# Transimpedance.net
KiCad netlist of a schematic drawn in Altium Designer
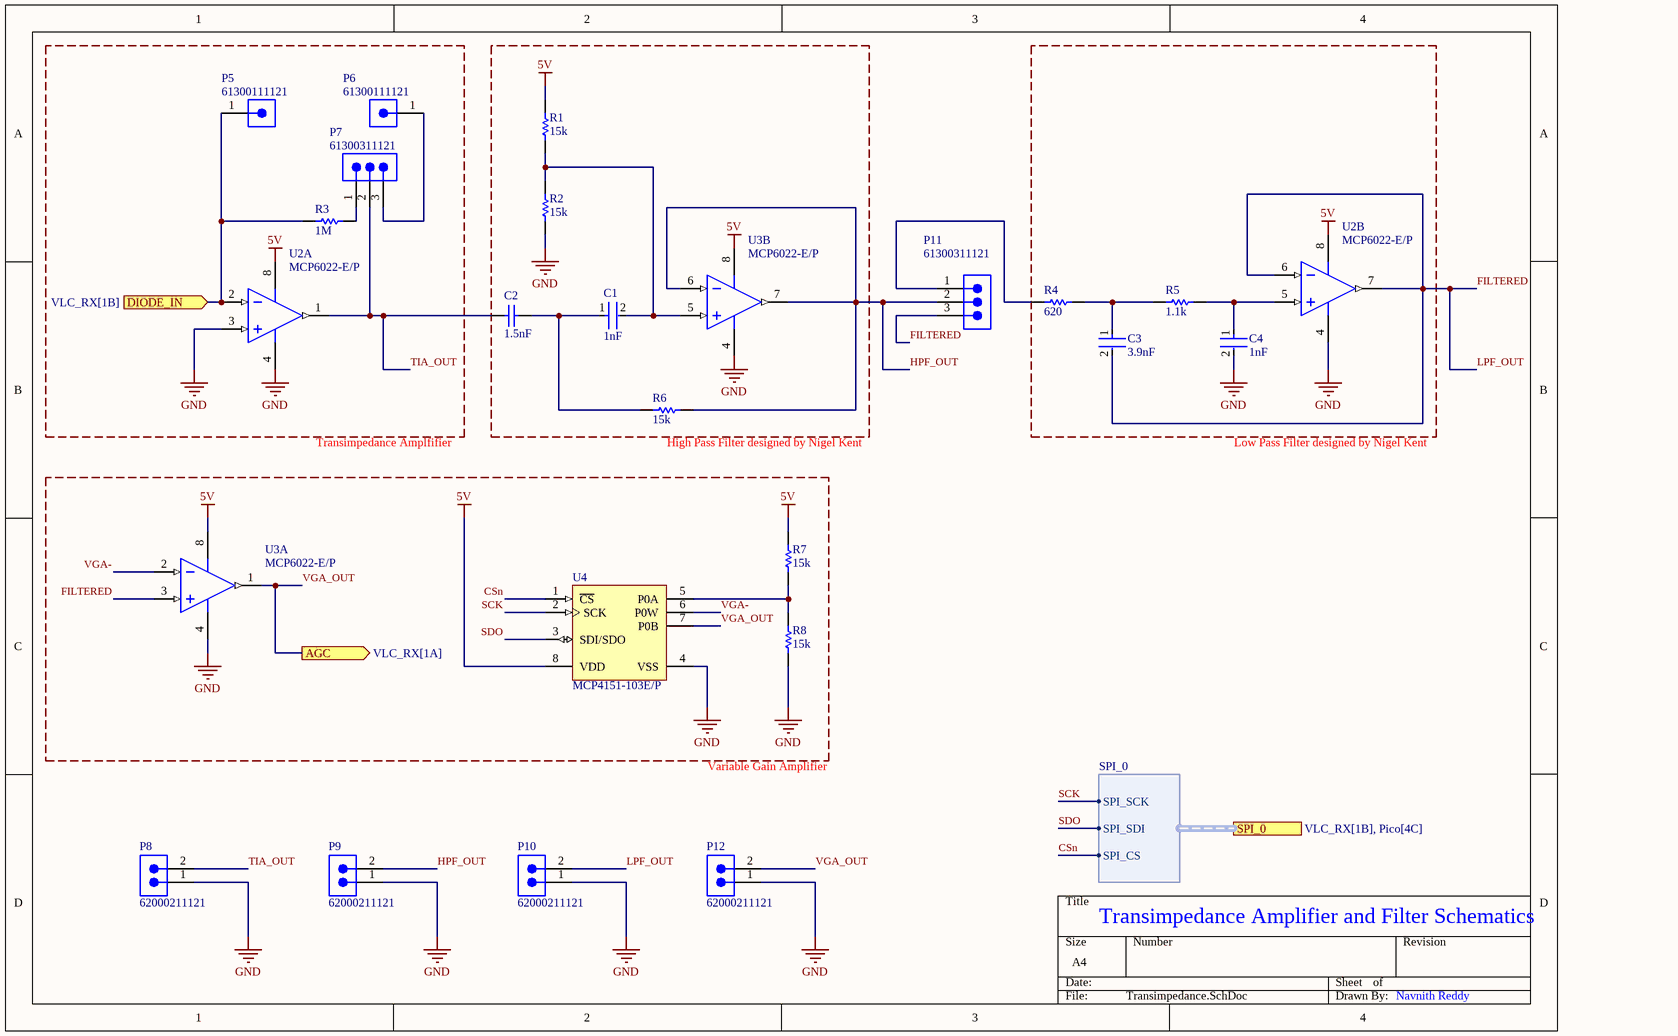
[diagram p0: Transimpedance.SchDoc]

(export (version "E")
  (design (tool "Eeschema 10.0.6"))
  (components
    (comp (ref "C1")
      (value "1nF")
      (footprint "FP-0805-L_2_01_0_2-W_1_25-IPC_C")
      (description "General Purpose Ceramic Capacitor, 0805, 1nF, 10%, X7R, 0.15, 50V")
      (fields (field (name "VOLTAGE") "50V") (field (name "TOLERANCE") "10%"))
      (libsource (lib "Altium Content Vault") (part "02cd4be3c70576c341d710602a673aa"))
    )
    (comp (ref "C2")
      (value "1.5nF")
      (footprint "CAPC2013X94X50ML20T25")
      (fields
        (field (name "MANUFACTURER") "AVX Interconnect / Elco")
        (field (name "PART NUMBER") "08051C152KAT2A")
      )
      (libsource (lib "Altium Content Vault") (part "CAP"))
    )
    (comp (ref "C3")
      (value "3.9nF")
      (footprint "FP-C0805C-DN-MFG")
      (description "C0805 3,900 pF C0G 30ppm/°C 5.00% 200 V")
      (fields (field (name "MANUFACTURER PART NUMBER") "C0805C392J2GACAUTO"))
      (libsource (lib "Altium Content Vault") (part "b4654b650e69147ec39a6b967a45e02"))
    )
    (comp (ref "C4")
      (value "1nF")
      (footprint "FP-0805-L_2_01_0_2-W_1_25-IPC_C")
      (description "General Purpose Ceramic Capacitor, 0805, 1nF, 10%, X7R, 0.15, 50V")
      (fields (field (name "VOLTAGE") "50V") (field (name "TOLERANCE") "10%"))
      (libsource (lib "Altium Content Vault") (part "02cd4be3c70576c341d710602a673aa"))
    )
    (comp (ref "P5")
      (value "61300111121")
      (footprint "61300111121")
      (libsource (lib "Altium Content Vault") (part "Header_Male_1R_01P"))
    )
    (comp (ref "P6")
      (value "61300111121")
      (footprint "61300111121")
      (libsource (lib "Altium Content Vault") (part "Header_Male_1R_01P"))
    )
    (comp (ref "P7")
      (value "61300311121")
      (footprint "61300311121")
      (libsource (lib "Altium Content Vault") (part "Header_Male_1R_03P"))
    )
    (comp (ref "P8")
      (value "62000211121")
      (footprint "62000211121")
      (libsource (lib "Altium Content Vault") (part "Header_Male_1R_02P"))
    )
    (comp (ref "P9")
      (value "62000211121")
      (footprint "62000211121")
      (libsource (lib "Altium Content Vault") (part "Header_Male_1R_02P"))
    )
    (comp (ref "P10")
      (value "62000211121")
      (footprint "62000211121")
      (libsource (lib "Altium Content Vault") (part "Header_Male_1R_02P"))
    )
    (comp (ref "P11")
      (value "61300311121")
      (footprint "61300311121")
      (libsource (lib "Altium Content Vault") (part "Header_Male_1R_03P"))
    )
    (comp (ref "P12")
      (value "62000211121")
      (footprint "62000211121")
      (libsource (lib "Altium Content Vault") (part "Header_Male_1R_02P"))
    )
    (comp (ref "R1")
      (value "15k")
      (footprint "RESC2013X55X40NL15T20")
      (fields (field (name "PART NUMBER") "TNPW080515K0BEEA") (field (name "MANUFACTURER") "Vishay Dale"))
      (libsource (lib "Altium Content Vault") (part "RES"))
    )
    (comp (ref "R2")
      (value "15k")
      (footprint "RESC2013X55X40NL15T20")
      (fields (field (name "PART NUMBER") "TNPW080515K0BEEA") (field (name "MANUFACTURER") "Vishay Dale"))
      (libsource (lib "Altium Content Vault") (part "RES"))
    )
    (comp (ref "R3")
      (value "1M")
      (footprint "RESC2013X60X40LL20T25")
      (fields (field (name "PART NUMBER") "ERA-6AEB105V") (field (name "MANUFACTURER") "Panasonic"))
      (libsource (lib "Altium Content Vault") (part "RES"))
    )
    (comp (ref "R4")
      (value "620")
      (footprint "RESC2013X70X40LL20T20")
      (fields (field (name "MANUFACTURER") "Panasonic") (field (name "PART NUMBER") "ERJ-6GEYJ621V"))
      (libsource (lib "Altium Content Vault") (part "RES"))
    )
    (comp (ref "R5")
      (value "1.1k")
      (footprint "RESC2013X50X30LL20T20")
      (fields (field (name "PART NUMBER") "CRCW08051K10FKTA") (field (name "MANUFACTURER") "Vishay Dale"))
      (libsource (lib "Altium Content Vault") (part "RES"))
    )
    (comp (ref "R6")
      (value "15k")
      (footprint "RESC2013X55X40NL15T20")
      (fields (field (name "PART NUMBER") "TNPW080515K0BEEA") (field (name "MANUFACTURER") "Vishay Dale"))
      (libsource (lib "Altium Content Vault") (part "RES"))
    )
    (comp (ref "R7")
      (value "15k")
      (footprint "RESC2013X55X40NL15T20")
      (fields (field (name "PART NUMBER") "TNPW080515K0BEEA") (field (name "MANUFACTURER") "Vishay Dale"))
      (libsource (lib "Altium Content Vault") (part "RES"))
    )
    (comp (ref "R8")
      (value "15k")
      (footprint "RESC2013X55X40NL15T20")
      (fields (field (name "PART NUMBER") "TNPW080515K0BEEA") (field (name "MANUFACTURER") "Vishay Dale"))
      (libsource (lib "Altium Content Vault") (part "RES"))
    )
    (comp (ref "U2")
      (value "MCP6022-E/P")
      (footprint "PDIP300-P8")
      (description "None")
      (libsource (lib "Altium Content Vault") (part "AMP-OPA-MCP6022-IL8"))
    )
    (comp (ref "U3")
      (value "MCP6022-E/P")
      (footprint "PDIP300-P8")
      (description "None")
      (libsource (lib "Altium Content Vault") (part "AMP-OPA-MCP6022-IL8"))
    )
    (comp (ref "U4")
      (value "MCP4151-103E/P")
      (footprint "PDIP300-P8")
      (description "7/8-Bit Single/Dual SPI Digital POT with Volatile Memory, 8-Pin PDIP, Extended Temperature")
      (libsource (lib "Altium Content Vault") (part "IN-DPOT-MCP41X1-8"))
    )
  )
  (nets
    (net (code "2") (name "/CSn") (class "Default")
      (node (ref "U4") (pin "1") (pinfunction "~{CS}_1") (pintype "input"))
    )
    (net (code "3") (name "/DIODE_IN") (class "Default")
      (node (ref "P5") (pin "1") (pinfunction "1_1") (pintype "passive"))
      (node (ref "R3") (pin "1") (pinfunction "1_1") (pintype "passive"))
      (node (ref "U2") (pin "2") (pinfunction "VINA-_2") (pintype "input"))
    )
    (net (code "4") (name "/FILTERED") (class "Default")
      (node (ref "C3") (pin "2") (pinfunction "2_2") (pintype "passive"))
      (node (ref "P10") (pin "2") (pinfunction "2_2") (pintype "passive"))
      (node (ref "P11") (pin "3") (pinfunction "3_3") (pintype "passive"))
      (node (ref "U2") (pin "6") (pinfunction "VINB-_6") (pintype "input"))
      (node (ref "U2") (pin "7") (pinfunction "VOUTB_7") (pintype "output"))
      (node (ref "U3") (pin "3") (pinfunction "VINA+_3") (pintype "input"))
    )
    (net (code "5") (name "/HPF_OUT") (class "Default")
      (node (ref "P11") (pin "2") (pinfunction "2_2") (pintype "passive"))
      (node (ref "P9") (pin "2") (pinfunction "2_2") (pintype "passive"))
      (node (ref "R6") (pin "2") (pinfunction "2_2") (pintype "passive"))
      (node (ref "U3") (pin "6") (pinfunction "VINB-_6") (pintype "input"))
      (node (ref "U3") (pin "7") (pinfunction "VOUTB_7") (pintype "output"))
    )
    (net (code "6") (name "/SCK") (class "Default")
      (node (ref "U4") (pin "2") (pinfunction "SCK_2") (pintype "input"))
    )
    (net (code "7") (name "/SDO") (class "Default")
      (node (ref "U4") (pin "3") (pinfunction "SDI/SDO_3") (pintype "bidirectional"))
    )
    (net (code "8") (name "/TIA_OUT") (class "Default")
      (node (ref "C2") (pin "1") (pinfunction "1_1") (pintype "passive"))
      (node (ref "P7") (pin "2") (pinfunction "2_2") (pintype "passive"))
      (node (ref "P8") (pin "2") (pinfunction "2_2") (pintype "passive"))
      (node (ref "U2") (pin "1") (pinfunction "VOUTA_1") (pintype "output"))
    )
    (net (code "9") (name "/VGA-") (class "Default")
      (node (ref "U3") (pin "2") (pinfunction "VINA-_2") (pintype "input"))
      (node (ref "U4") (pin "6") (pinfunction "P0W_6") (pintype "passive"))
    )
    (net (code "10") (name "/VGA_OUT") (class "Default")
      (node (ref "P12") (pin "2") (pinfunction "2_2") (pintype "passive"))
      (node (ref "U3") (pin "1") (pinfunction "VOUTA_1") (pintype "output"))
      (node (ref "U4") (pin "7") (pinfunction "P0B_7") (pintype "passive"))
    )
    (net (code "12") (name "5V") (class "Default")
      (node (ref "R1") (pin "2") (pinfunction "2_2") (pintype "passive"))
      (node (ref "R7") (pin "2") (pinfunction "2_2") (pintype "passive"))
      (node (ref "U2") (pin "8") (pinfunction "VDD_8") (pintype "power_in"))
      (node (ref "U3") (pin "8") (pinfunction "VDD_8") (pintype "power_in"))
      (node (ref "U4") (pin "8") (pinfunction "VDD_8") (pintype "power_in"))
    )
    (net (code "13") (name "GND") (class "Default")
      (node (ref "C4") (pin "2") (pinfunction "2_2") (pintype "passive"))
      (node (ref "P10") (pin "1") (pinfunction "1_1") (pintype "passive"))
      (node (ref "P12") (pin "1") (pinfunction "1_1") (pintype "passive"))
      (node (ref "P8") (pin "1") (pinfunction "1_1") (pintype "passive"))
      (node (ref "P9") (pin "1") (pinfunction "1_1") (pintype "passive"))
      (node (ref "R2") (pin "1") (pinfunction "1_1") (pintype "passive"))
      (node (ref "R8") (pin "1") (pinfunction "1_1") (pintype "passive"))
      (node (ref "U2") (pin "3") (pinfunction "VINA+_3") (pintype "input"))
      (node (ref "U2") (pin "4") (pinfunction "VSS_4") (pintype "power_in"))
      (node (ref "U3") (pin "4") (pinfunction "VSS_4") (pintype "power_in"))
      (node (ref "U4") (pin "4") (pinfunction "VSS_4") (pintype "power_in"))
    )
    (net (code "14") (name "Net-(C1-Pad1)") (class "Default")
      (node (ref "C1") (pin "1") (pinfunction "1_1") (pintype "passive"))
      (node (ref "C2") (pin "2") (pinfunction "2_2") (pintype "passive"))
      (node (ref "R6") (pin "1") (pinfunction "1_1") (pintype "passive"))
    )
    (net (code "15") (name "Net-(C3-Pad1)") (class "Default")
      (node (ref "C3") (pin "1") (pinfunction "1_1") (pintype "passive"))
      (node (ref "R4") (pin "2") (pinfunction "2_2") (pintype "passive"))
      (node (ref "R5") (pin "1") (pinfunction "1_1") (pintype "passive"))
    )
    (net (code "16") (name "Net-(P6-Pad1)") (class "Default")
      (node (ref "P6") (pin "1") (pinfunction "1_1") (pintype "passive"))
      (node (ref "P7") (pin "3") (pinfunction "3_3") (pintype "passive"))
    )
    (net (code "17") (name "Net-(P7-Pad1)") (class "Default")
      (node (ref "P7") (pin "1") (pinfunction "1_1") (pintype "passive"))
      (node (ref "R3") (pin "2") (pinfunction "2_2") (pintype "passive"))
    )
    (net (code "18") (name "Net-(P11-Pad1)") (class "Default")
      (node (ref "P11") (pin "1") (pinfunction "1_1") (pintype "passive"))
      (node (ref "R4") (pin "1") (pinfunction "1_1") (pintype "passive"))
    )
    (net (code "19") (name "Net-(U2B-VINB+)") (class "Default")
      (node (ref "C4") (pin "1") (pinfunction "1_1") (pintype "passive"))
      (node (ref "R5") (pin "2") (pinfunction "2_2") (pintype "passive"))
      (node (ref "U2") (pin "5") (pinfunction "VINB+_5") (pintype "input"))
    )
    (net (code "20") (name "Net-(U3B-VINB+)") (class "Default")
      (node (ref "C1") (pin "2") (pinfunction "2_2") (pintype "passive"))
      (node (ref "R1") (pin "1") (pinfunction "1_1") (pintype "passive"))
      (node (ref "R2") (pin "2") (pinfunction "2_2") (pintype "passive"))
      (node (ref "U3") (pin "5") (pinfunction "VINB+_5") (pintype "input"))
    )
    (net (code "21") (name "Net-(U4-P0A)") (class "Default")
      (node (ref "R7") (pin "1") (pinfunction "1_1") (pintype "passive"))
      (node (ref "R8") (pin "2") (pinfunction "2_2") (pintype "passive"))
      (node (ref "U4") (pin "5") (pinfunction "P0A_5") (pintype "passive"))
    )
  )
)
